# demo.net
KiCad netlist of a schematic drawn in EAGLE
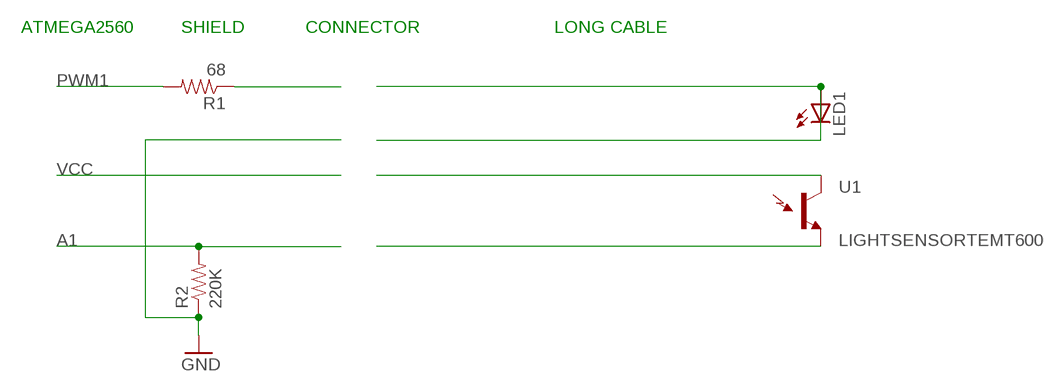
[diagram p0: schematic, sheet 1]

(export (version "E")
  (design (tool "Eeschema 10.0.6"))
  (components
    (comp (ref "LED1")
      (value "LED3MM")
      (footprint "eagle-import:LED3MM")
      (libsource (lib "eagle-import") (part "LED3MM"))
    )
    (comp (ref "R1")
      (value "68")
      (footprint "eagle-import:R2512")
      (libsource (lib "eagle-import") (part "RESISTOR2512"))
    )
    (comp (ref "R2")
      (value "220K")
      (footprint "eagle-import:R2512")
      (libsource (lib "eagle-import") (part "RESISTOR2512"))
    )
    (comp (ref "U1")
      (value "LIGHTSENSORTEMT6000")
      (footprint "eagle-import:TEMT6000-SEN")
      (libsource (lib "eagle-import") (part "LIGHTSENSORTEMT6000"))
    )
  )
  (nets
    (net (code "1") (name "/A1") (class "Default")
      (node (ref "R2") (pin "2") (pinfunction "2_2") (pintype "passive"))
    )
    (net (code "2") (name "/PWM1") (class "Default")
      (node (ref "R1") (pin "2") (pinfunction "2_2") (pintype "passive"))
    )
    (net (code "4") (name "GND") (class "Default")
      (node (ref "R2") (pin "1") (pinfunction "1_1") (pintype "passive"))
    )
    (net (code "5") (name "Net-(LED1-C)") (class "Default")
      (node (ref "LED1") (pin "A") (pinfunction "A_A") (pintype "passive"))
      (node (ref "LED1") (pin "K") (pinfunction "C_K") (pintype "passive"))
    )
    (net (code "6") (name "unconnected-(R1-Pad1)") (class "Default")
      (node (ref "R1") (pin "1") (pinfunction "1_1") (pintype "passive"))
    )
    (net (code "7") (name "unconnected-(U1-C1-PadCOLLECTOR)") (class "Default")
      (node (ref "U1") (pin "COLLECTOR") (pinfunction "C1_COLLECTOR") (pintype "passive"))
    )
    (net (code "8") (name "unconnected-(U1-E1-PadEMITTER)") (class "Default")
      (node (ref "U1") (pin "EMITTER") (pinfunction "E1_EMITTER") (pintype "passive"))
    )
  )
)
